# MSP430.net
KiCad netlist of a schematic drawn in Altium Designer
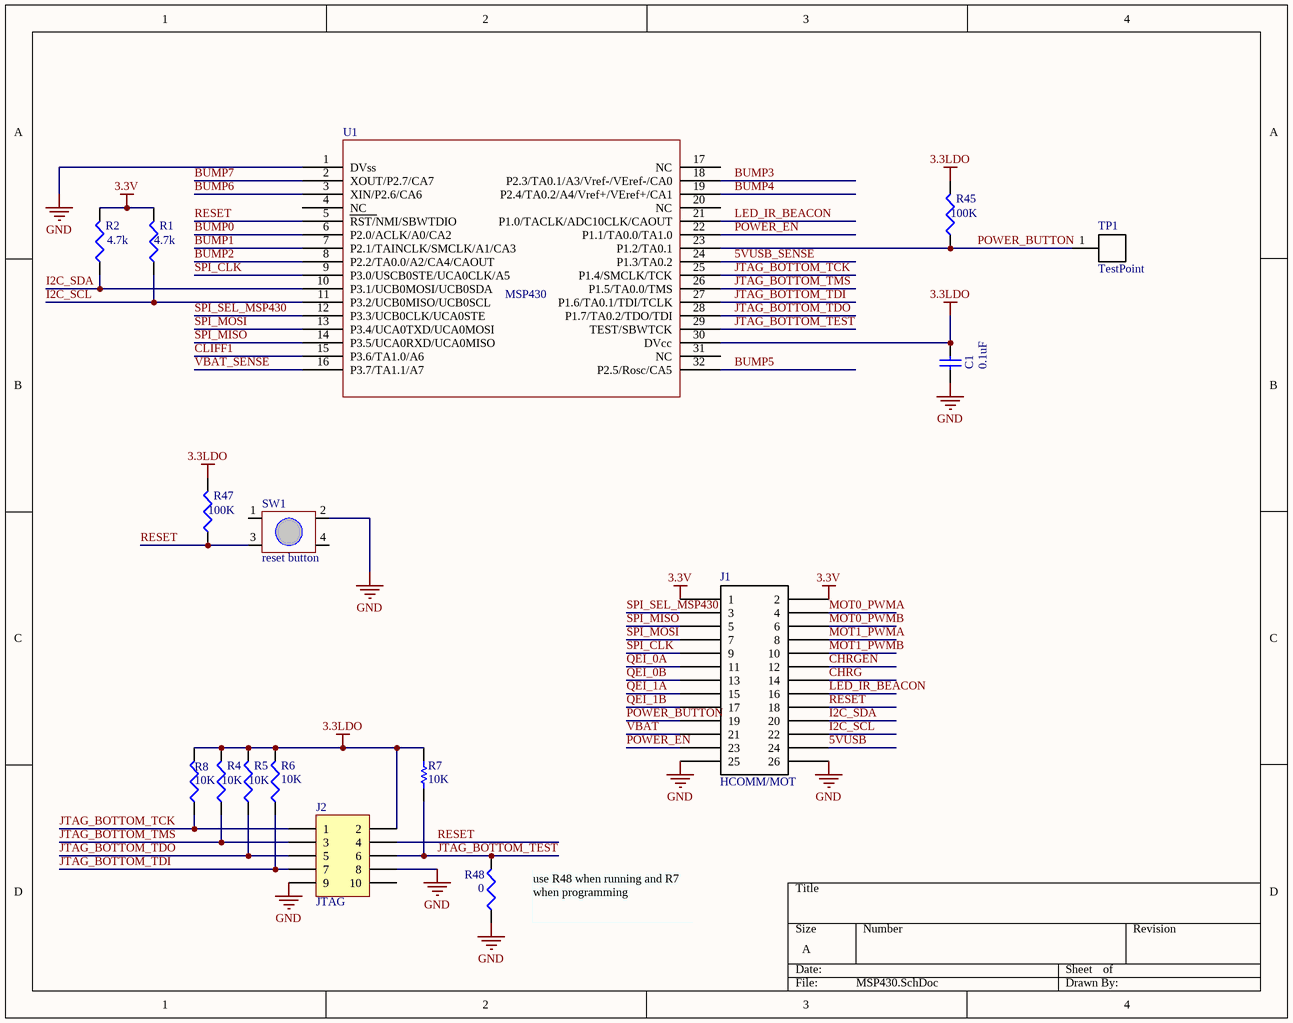
[diagram p0: MSP430.SchDoc]

(export (version "E")
  (design (tool "Eeschema 10.0.6"))
  (components
    (comp (ref "C1")
      (value "0.1uF")
      (footprint "CAPC1005L")
      (description "Capacitor (Semiconductor SIM Model)")
      (fields (field (name "Comment") "Cap Semi") (field (name "PUBLISHER") "Altium Limited"))
      (libsource (lib "Miscellaneous Devices") (part "Cap Semi"))
    )
    (comp (ref "J1")
      (value "HCOMM/MOT")
      (footprint "HeaderSM 13x2")
      (description "Header, 2X20, 50mil, IDC")
      (libsource (lib "mrone") (part "HCOMM/HMOT"))
    )
    (comp (ref "J2")
      (value "JTAG")
      (footprint "HDR2X5")
      (description "Header, 5-Pin, Dual row")
      (fields (field (name "PUBLISHER") "Altium Limited"))
      (libsource (lib "Miscellaneous Connectors") (part "Header 5X2"))
    )
    (comp (ref "R1")
      (value "4.7k")
      (footprint "RESC1608L")
      (description "Resistor")
      (fields (field (name "Comment") "Res3") (field (name "PUBLISHER") "Altium Limited"))
      (libsource (lib "Miscellaneous Devices") (part "Res3"))
    )
    (comp (ref "R2")
      (value "4.7k")
      (footprint "RESC1608L")
      (description "Resistor")
      (fields (field (name "Comment") "Res3") (field (name "PUBLISHER") "Altium Limited"))
      (libsource (lib "Miscellaneous Devices") (part "Res3"))
    )
    (comp (ref "R4")
      (value "10K")
      (footprint "RESC1608L")
      (description "Resistor")
      (fields (field (name "Comment") "Res3") (field (name "PUBLISHER") "Altium Limited"))
      (libsource (lib "Miscellaneous Devices") (part "Res3"))
    )
    (comp (ref "R5")
      (value "10K")
      (footprint "RESC1608L")
      (description "Resistor")
      (fields (field (name "Comment") "Res3") (field (name "PUBLISHER") "Altium Limited"))
      (libsource (lib "Miscellaneous Devices") (part "Res3"))
    )
    (comp (ref "R6")
      (value "10K")
      (footprint "RESC1608L")
      (description "Resistor")
      (fields (field (name "Comment") "Res3") (field (name "PUBLISHER") "Altium Limited"))
      (libsource (lib "Miscellaneous Devices") (part "Res3"))
    )
    (comp (ref "R7")
      (value "10K")
      (footprint "RESC1608L")
      (description "Semiconductor Resistor")
      (fields (field (name "Comment") "Res Semi") (field (name "PUBLISHER") "Altium Limited"))
      (libsource (lib "Miscellaneous Devices") (part "Res Semi"))
    )
    (comp (ref "R8")
      (value "10K")
      (footprint "RESC1608L")
      (description "Resistor")
      (fields (field (name "Comment") "Res3") (field (name "PUBLISHER") "Altium Limited"))
      (libsource (lib "Miscellaneous Devices") (part "Res3"))
    )
    (comp (ref "R45")
      (value "100K")
      (footprint "RESC1608L")
      (description "Resistor")
      (fields (field (name "Comment") "Res3") (field (name "PUBLISHER") "Altium Limited"))
      (libsource (lib "Miscellaneous Devices") (part "Res3"))
    )
    (comp (ref "R47")
      (value "100K")
      (footprint "RESC1608L")
      (description "Resistor")
      (fields (field (name "Comment") "Res3") (field (name "PUBLISHER") "Altium Limited"))
      (libsource (lib "Miscellaneous Devices") (part "Res3"))
    )
    (comp (ref "R48")
      (value "0")
      (footprint "RESC1608L")
      (description "Resistor")
      (fields (field (name "Comment") "Res3") (field (name "PUBLISHER") "Altium Limited"))
      (libsource (lib "Miscellaneous Devices") (part "Res3"))
    )
    (comp (ref "SW1")
      (value "reset button")
      (footprint "SwitchTall-TL330")
      (libsource (lib "mrone") (part "Switch-TL330"))
    )
    (comp (ref "TP1")
      (value "TestPoint")
      (footprint "TestPoint")
      (libsource (lib "mrone") (part "TestPoint"))
    )
    (comp (ref "U1")
      (value "MSP430")
      (footprint "MSP430_32PIN")
      (libsource (lib "mrone") (part "MSP430_32pin"))
    )
  )
  (nets
    (net (code "1") (name "/5VUSB") (class "Default")
      (node (ref "J1") (pin "24") (pinfunction "24_24") (pintype "passive"))
    )
    (net (code "2") (name "/5VUSB_SENSE") (class "Default")
      (node (ref "U1") (pin "24") (pinfunction "P1.3/TA0.2_24") (pintype "passive"))
    )
    (net (code "3") (name "/BUMP0") (class "Default")
      (node (ref "U1") (pin "6") (pinfunction "P2.0/ACLK/A0/CA2_6") (pintype "passive"))
    )
    (net (code "4") (name "/BUMP1") (class "Default")
      (node (ref "U1") (pin "7") (pinfunction "P2.1/TAINCLK/SMCLK/A1/CA3_7") (pintype "passive"))
    )
    (net (code "5") (name "/BUMP2") (class "Default")
      (node (ref "U1") (pin "8") (pinfunction "P2.2/TA0.0/A2/CA4/CAOUT_8") (pintype "passive"))
    )
    (net (code "6") (name "/BUMP3") (class "Default")
      (node (ref "U1") (pin "18") (pinfunction "P2.3/TA0.1/A3/Vref-/VEref-/CA0_18") (pintype "passive"))
    )
    (net (code "7") (name "/BUMP4") (class "Default")
      (node (ref "U1") (pin "19") (pinfunction "P2.4/TA0.2/A4/Vref+/VEref+/CA1_19") (pintype "passive"))
    )
    (net (code "8") (name "/BUMP5") (class "Default")
      (node (ref "U1") (pin "32") (pinfunction "P2.5/Rosc/CA5_32") (pintype "passive"))
    )
    (net (code "9") (name "/BUMP6") (class "Default")
      (node (ref "U1") (pin "3") (pinfunction "XIN/P2.6/CA6_3") (pintype "passive"))
    )
    (net (code "10") (name "/BUMP7") (class "Default")
      (node (ref "U1") (pin "2") (pinfunction "XOUT/P2.7/CA7_2") (pintype "passive"))
    )
    (net (code "11") (name "/CHRG") (class "Default")
      (node (ref "J1") (pin "14") (pinfunction "14_14") (pintype "passive"))
    )
    (net (code "12") (name "/CHRGEN") (class "Default")
      (node (ref "J1") (pin "12") (pinfunction "12_12") (pintype "passive"))
    )
    (net (code "13") (name "/CLIFF1") (class "Default")
      (node (ref "U1") (pin "15") (pinfunction "P3.6/TA1.0/A6_15") (pintype "passive"))
    )
    (net (code "14") (name "/I2C_SCL") (class "Default")
      (node (ref "J1") (pin "22") (pinfunction "22_22") (pintype "passive"))
      (node (ref "R1") (pin "1") (pinfunction "1_1") (pintype "passive"))
      (node (ref "U1") (pin "11") (pinfunction "P3.2/UCB0MISO/UCB0SCL_11") (pintype "passive"))
    )
    (net (code "15") (name "/I2C_SDA") (class "Default")
      (node (ref "J1") (pin "20") (pinfunction "20_20") (pintype "passive"))
      (node (ref "R2") (pin "1") (pinfunction "1_1") (pintype "passive"))
      (node (ref "U1") (pin "10") (pinfunction "P3.1/UCB0MOSI/UCB0SDA_10") (pintype "passive"))
    )
    (net (code "16") (name "/JTAG_BOTTOM_TCK") (class "Default")
      (node (ref "J2") (pin "1") (pinfunction "1_1") (pintype "passive"))
      (node (ref "R8") (pin "1") (pinfunction "1_1") (pintype "passive"))
      (node (ref "U1") (pin "25") (pinfunction "P1.4/SMCLK/TCK_25") (pintype "passive"))
    )
    (net (code "17") (name "/JTAG_BOTTOM_TDI") (class "Default")
      (node (ref "J2") (pin "7") (pinfunction "7_7") (pintype "passive"))
      (node (ref "R6") (pin "1") (pinfunction "1_1") (pintype "passive"))
      (node (ref "U1") (pin "27") (pinfunction "P1.6/TA0.1/TDI/TCLK_27") (pintype "passive"))
    )
    (net (code "18") (name "/JTAG_BOTTOM_TDO") (class "Default")
      (node (ref "J2") (pin "5") (pinfunction "5_5") (pintype "passive"))
      (node (ref "R5") (pin "1") (pinfunction "1_1") (pintype "passive"))
      (node (ref "U1") (pin "28") (pinfunction "P1.7/TA0.2/TDO/TDI_28") (pintype "passive"))
    )
    (net (code "19") (name "/JTAG_BOTTOM_TEST") (class "Default")
      (node (ref "J2") (pin "6") (pinfunction "6_6") (pintype "passive"))
      (node (ref "R48") (pin "2") (pinfunction "2_2") (pintype "passive"))
      (node (ref "R7") (pin "1") (pinfunction "1_1") (pintype "passive"))
      (node (ref "U1") (pin "29") (pinfunction "TEST/SBWTCK_29") (pintype "passive"))
    )
    (net (code "20") (name "/JTAG_BOTTOM_TMS") (class "Default")
      (node (ref "J2") (pin "3") (pinfunction "3_3") (pintype "passive"))
      (node (ref "R4") (pin "1") (pinfunction "1_1") (pintype "passive"))
      (node (ref "U1") (pin "26") (pinfunction "P1.5/TA0.0/TMS_26") (pintype "passive"))
    )
    (net (code "21") (name "/LED_IR_BEACON") (class "Default")
      (node (ref "J1") (pin "16") (pinfunction "16_16") (pintype "passive"))
      (node (ref "U1") (pin "21") (pinfunction "P1.0/TACLK/ADC10CLK/CAOUT_21") (pintype "passive"))
    )
    (net (code "22") (name "/MOT0_PWMA") (class "Default")
      (node (ref "J1") (pin "4") (pinfunction "4_4") (pintype "passive"))
    )
    (net (code "23") (name "/MOT0_PWMB") (class "Default")
      (node (ref "J1") (pin "6") (pinfunction "6_6") (pintype "passive"))
    )
    (net (code "24") (name "/MOT1_PWMA") (class "Default")
      (node (ref "J1") (pin "8") (pinfunction "8_8") (pintype "passive"))
    )
    (net (code "25") (name "/MOT1_PWMB") (class "Default")
      (node (ref "J1") (pin "10") (pinfunction "10_10") (pintype "passive"))
    )
    (net (code "26") (name "/POWER_BUTTON") (class "Default")
      (node (ref "J1") (pin "19") (pinfunction "19_19") (pintype "passive"))
      (node (ref "R45") (pin "1") (pinfunction "1_1") (pintype "passive"))
      (node (ref "TP1") (pin "1") (pintype "passive"))
      (node (ref "U1") (pin "23") (pinfunction "P1.2/TA0.1_23") (pintype "passive"))
    )
    (net (code "27") (name "/POWER_EN") (class "Default")
      (node (ref "J1") (pin "23") (pinfunction "23_23") (pintype "passive"))
      (node (ref "U1") (pin "22") (pinfunction "P1.1/TA0.0/TA1.0_22") (pintype "passive"))
    )
    (net (code "28") (name "/QEI_0A") (class "Default")
      (node (ref "J1") (pin "11") (pinfunction "11_11") (pintype "passive"))
    )
    (net (code "29") (name "/QEI_0B") (class "Default")
      (node (ref "J1") (pin "13") (pinfunction "13_13") (pintype "passive"))
    )
    (net (code "30") (name "/QEI_1A") (class "Default")
      (node (ref "J1") (pin "15") (pinfunction "15_15") (pintype "passive"))
    )
    (net (code "31") (name "/QEI_1B") (class "Default")
      (node (ref "J1") (pin "17") (pinfunction "17_17") (pintype "passive"))
    )
    (net (code "32") (name "/RESET") (class "Default")
      (node (ref "J1") (pin "18") (pinfunction "18_18") (pintype "passive"))
      (node (ref "J2") (pin "4") (pinfunction "4_4") (pintype "passive"))
      (node (ref "R47") (pin "1") (pinfunction "1_1") (pintype "passive"))
      (node (ref "SW1") (pin "3") (pinfunction "3_3") (pintype "passive"))
      (node (ref "U1") (pin "5") (pinfunction "RST/NMI/SBWTDIO_5") (pintype "passive"))
    )
    (net (code "33") (name "/SPI_CLK") (class "Default")
      (node (ref "J1") (pin "9") (pinfunction "9_9") (pintype "passive"))
      (node (ref "U1") (pin "9") (pinfunction "P3.0/USCB0STE/UCA0CLK/A5_9") (pintype "passive"))
    )
    (net (code "34") (name "/SPI_MISO") (class "Default")
      (node (ref "J1") (pin "5") (pinfunction "5_5") (pintype "passive"))
      (node (ref "U1") (pin "14") (pinfunction "P3.5/UCA0RXD/UCA0MISO_14") (pintype "passive"))
    )
    (net (code "35") (name "/SPI_MOSI") (class "Default")
      (node (ref "J1") (pin "7") (pinfunction "7_7") (pintype "passive"))
      (node (ref "U1") (pin "13") (pinfunction "P3.4/UCA0TXD/UCA0MOSI_13") (pintype "passive"))
    )
    (net (code "36") (name "/SPI_SEL_MSP430") (class "Default")
      (node (ref "J1") (pin "3") (pinfunction "3_3") (pintype "passive"))
      (node (ref "U1") (pin "12") (pinfunction "P3.3/UCB0CLK/UCA0STE_12") (pintype "passive"))
    )
    (net (code "37") (name "/VBAT") (class "Default")
      (node (ref "J1") (pin "21") (pinfunction "21_21") (pintype "passive"))
    )
    (net (code "38") (name "/VBAT_SENSE") (class "Default")
      (node (ref "U1") (pin "16") (pinfunction "P3.7/TA1.1/A7_16") (pintype "passive"))
    )
    (net (code "39") (name "3.3LDO") (class "Default")
      (node (ref "C1") (pin "2") (pinfunction "2_2") (pintype "passive"))
      (node (ref "J2") (pin "2") (pinfunction "2_2") (pintype "passive"))
      (node (ref "R4") (pin "2") (pinfunction "2_2") (pintype "passive"))
      (node (ref "R45") (pin "2") (pinfunction "2_2") (pintype "passive"))
      (node (ref "R47") (pin "2") (pinfunction "2_2") (pintype "passive"))
      (node (ref "R5") (pin "2") (pinfunction "2_2") (pintype "passive"))
      (node (ref "R6") (pin "2") (pinfunction "2_2") (pintype "passive"))
      (node (ref "R7") (pin "2") (pinfunction "2_2") (pintype "passive"))
      (node (ref "R8") (pin "2") (pinfunction "2_2") (pintype "passive"))
      (node (ref "U1") (pin "30") (pinfunction "DVcc_30") (pintype "passive"))
    )
    (net (code "40") (name "3.3V") (class "Default")
      (node (ref "J1") (pin "1") (pinfunction "1_1") (pintype "passive"))
      (node (ref "J1") (pin "2") (pinfunction "2_2") (pintype "passive"))
      (node (ref "R1") (pin "2") (pinfunction "2_2") (pintype "passive"))
      (node (ref "R2") (pin "2") (pinfunction "2_2") (pintype "passive"))
    )
    (net (code "41") (name "GND") (class "Default")
      (node (ref "C1") (pin "1") (pinfunction "1_1") (pintype "passive"))
      (node (ref "J1") (pin "25") (pinfunction "25_25") (pintype "passive"))
      (node (ref "J1") (pin "26") (pinfunction "26_26") (pintype "passive"))
      (node (ref "J2") (pin "8") (pinfunction "8_8") (pintype "passive"))
      (node (ref "J2") (pin "9") (pinfunction "9_9") (pintype "passive"))
      (node (ref "R48") (pin "1") (pinfunction "1_1") (pintype "passive"))
      (node (ref "SW1") (pin "2") (pinfunction "2_2") (pintype "passive"))
      (node (ref "U1") (pin "1") (pinfunction "DVss_1") (pintype "passive"))
    )
    (net (code "42") (name "unconnected-(J2-Pad10)") (class "Default")
      (node (ref "J2") (pin "10") (pinfunction "10_10") (pintype "passive"))
    )
    (net (code "43") (name "unconnected-(SW1-Pad1)") (class "Default")
      (node (ref "SW1") (pin "1") (pinfunction "1_1") (pintype "passive"))
    )
    (net (code "44") (name "unconnected-(SW1-Pad4)") (class "Default")
      (node (ref "SW1") (pin "4") (pinfunction "4_4") (pintype "passive"))
    )
    (net (code "45") (name "unconnected-(U1-NC-Pad4)") (class "Default")
      (node (ref "U1") (pin "4") (pinfunction "NC_4") (pintype "passive"))
    )
    (net (code "46") (name "unconnected-(U1-NC-Pad17)") (class "Default")
      (node (ref "U1") (pin "17") (pinfunction "NC_17") (pintype "passive"))
    )
    (net (code "47") (name "unconnected-(U1-NC-Pad20)") (class "Default")
      (node (ref "U1") (pin "20") (pinfunction "NC_20") (pintype "passive"))
    )
    (net (code "48") (name "unconnected-(U1-NC-Pad31)") (class "Default")
      (node (ref "U1") (pin "31") (pinfunction "NC_31") (pintype "passive"))
    )
  )
)
